# P27.net
KiCad netlist of a schematic drawn in EAGLE
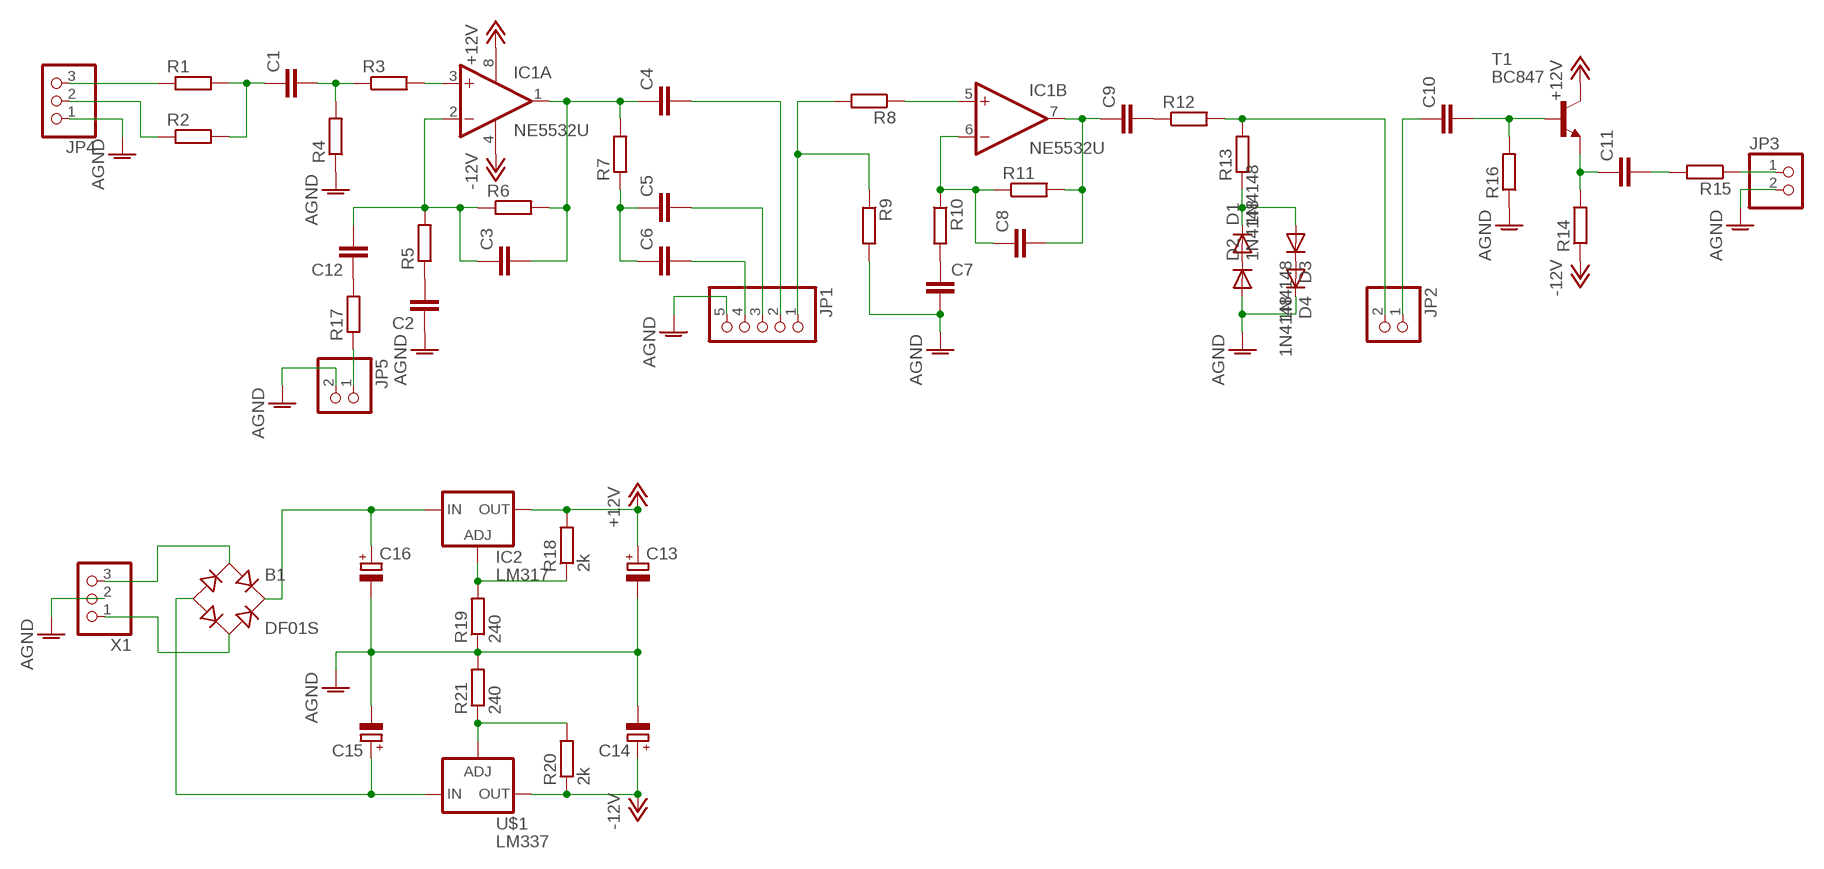
[diagram p0: schematic, sheet 1]

(export (version "E")
  (design (tool "Eeschema 10.0.6"))
  (components
    (comp (ref "B1")
      (value "DF01S")
      (footprint "eagle-import:DFS")
      (libsource (lib "eagle-import") (part "DFS01"))
    )
    (comp (ref "C1")
      (value "C-EUC0805K")
      (footprint "eagle-import:C0805K")
      (libsource (lib "eagle-import") (part "C-EUC0805K"))
    )
    (comp (ref "C2")
      (value "C-EUC0805K")
      (footprint "eagle-import:C0805K")
      (libsource (lib "eagle-import") (part "C-EUC0805K"))
    )
    (comp (ref "C3")
      (value "C-EUC0805K")
      (footprint "eagle-import:C0805K")
      (libsource (lib "eagle-import") (part "C-EUC0805K"))
    )
    (comp (ref "C4")
      (value "C-EUC0805K")
      (footprint "eagle-import:C0805K")
      (libsource (lib "eagle-import") (part "C-EUC0805K"))
    )
    (comp (ref "C5")
      (value "C-EUC0805K")
      (footprint "eagle-import:C0805K")
      (libsource (lib "eagle-import") (part "C-EUC0805K"))
    )
    (comp (ref "C6")
      (value "C-EUC0805K")
      (footprint "eagle-import:C0805K")
      (libsource (lib "eagle-import") (part "C-EUC0805K"))
    )
    (comp (ref "C7")
      (value "C-EUC0805K")
      (footprint "eagle-import:C0805K")
      (libsource (lib "eagle-import") (part "C-EUC0805K"))
    )
    (comp (ref "C8")
      (value "C-EUC0805K")
      (footprint "eagle-import:C0805K")
      (libsource (lib "eagle-import") (part "C-EUC0805K"))
    )
    (comp (ref "C9")
      (value "C-EUC0805K")
      (footprint "eagle-import:C0805K")
      (libsource (lib "eagle-import") (part "C-EUC0805K"))
    )
    (comp (ref "C10")
      (value "C-EUC0805K")
      (footprint "eagle-import:C0805K")
      (libsource (lib "eagle-import") (part "C-EUC0805K"))
    )
    (comp (ref "C11")
      (value "C-EUC0805K")
      (footprint "eagle-import:C0805K")
      (libsource (lib "eagle-import") (part "C-EUC0805K"))
    )
    (comp (ref "C12")
      (value "C-EUC0805K")
      (footprint "eagle-import:C0805K")
      (libsource (lib "eagle-import") (part "C-EUC0805K"))
    )
    (comp (ref "C13")
      (value "CPOL-EUD")
      (footprint "eagle-import:PANASONIC_D")
      (libsource (lib "eagle-import") (part "CPOL-EUD"))
    )
    (comp (ref "C14")
      (value "CPOL-EUD")
      (footprint "eagle-import:PANASONIC_D")
      (libsource (lib "eagle-import") (part "CPOL-EUD"))
    )
    (comp (ref "C15")
      (value "CPOL-EUD")
      (footprint "eagle-import:PANASONIC_D")
      (libsource (lib "eagle-import") (part "CPOL-EUD"))
    )
    (comp (ref "C16")
      (value "CPOL-EUD")
      (footprint "eagle-import:PANASONIC_D")
      (libsource (lib "eagle-import") (part "CPOL-EUD"))
    )
    (comp (ref "D1")
      (value "1N4148")
      (footprint "eagle-import:D0805")
      (libsource (lib "eagle-import") (part "1N4148"))
    )
    (comp (ref "D2")
      (value "1N4148")
      (footprint "eagle-import:D0805")
      (libsource (lib "eagle-import") (part "1N4148"))
    )
    (comp (ref "D3")
      (value "1N4148")
      (footprint "eagle-import:D0805")
      (libsource (lib "eagle-import") (part "1N4148"))
    )
    (comp (ref "D4")
      (value "1N4148")
      (footprint "eagle-import:D0805")
      (libsource (lib "eagle-import") (part "1N4148"))
    )
    (comp (ref "IC1")
      (value "NE5532U")
      (footprint "eagle-import:SO08")
      (libsource (lib "eagle-import") (part "NE5532U"))
    )
    (comp (ref "IC2")
      (value "LM317")
      (footprint "eagle-import:SOT223")
      (libsource (lib "eagle-import") (part "LM317"))
    )
    (comp (ref "JP1")
      (value "PINHD-1X5")
      (footprint "eagle-import:1X05")
      (libsource (lib "eagle-import") (part "PINHD-1X5"))
    )
    (comp (ref "JP2")
      (value "PINHD-1X2")
      (footprint "eagle-import:1X02")
      (libsource (lib "eagle-import") (part "PINHD-1X2"))
    )
    (comp (ref "JP3")
      (value "PINHD-1X2")
      (footprint "eagle-import:1X02")
      (libsource (lib "eagle-import") (part "PINHD-1X2"))
    )
    (comp (ref "JP4")
      (value "PINHD-1X3180")
      (footprint "eagle-import:1X03")
      (libsource (lib "eagle-import") (part "PINHD-1X3180"))
    )
    (comp (ref "JP5")
      (value "PINHD-1X2")
      (footprint "eagle-import:1X02")
      (libsource (lib "eagle-import") (part "PINHD-1X2"))
    )
    (comp (ref "R1")
      (value "R-EU_0805")
      (footprint "eagle-import:R0805")
      (libsource (lib "eagle-import") (part "R-EU_0805"))
    )
    (comp (ref "R2")
      (value "R-EU_0805")
      (footprint "eagle-import:R0805")
      (libsource (lib "eagle-import") (part "R-EU_0805"))
    )
    (comp (ref "R3")
      (value "R-EU_0805")
      (footprint "eagle-import:R0805")
      (libsource (lib "eagle-import") (part "R-EU_0805"))
    )
    (comp (ref "R4")
      (value "R-EU_0805")
      (footprint "eagle-import:R0805")
      (libsource (lib "eagle-import") (part "R-EU_0805"))
    )
    (comp (ref "R5")
      (value "R-EU_0805")
      (footprint "eagle-import:R0805")
      (libsource (lib "eagle-import") (part "R-EU_0805"))
    )
    (comp (ref "R6")
      (value "R-EU_0805")
      (footprint "eagle-import:R0805")
      (libsource (lib "eagle-import") (part "R-EU_0805"))
    )
    (comp (ref "R7")
      (value "R-EU_0805")
      (footprint "eagle-import:R0805")
      (libsource (lib "eagle-import") (part "R-EU_0805"))
    )
    (comp (ref "R8")
      (value "R-EU_0805")
      (footprint "eagle-import:R0805")
      (libsource (lib "eagle-import") (part "R-EU_0805"))
    )
    (comp (ref "R9")
      (value "R-EU_0805")
      (footprint "eagle-import:R0805")
      (libsource (lib "eagle-import") (part "R-EU_0805"))
    )
    (comp (ref "R10")
      (value "R-EU_0805")
      (footprint "eagle-import:R0805")
      (libsource (lib "eagle-import") (part "R-EU_0805"))
    )
    (comp (ref "R11")
      (value "R-EU_0805")
      (footprint "eagle-import:R0805")
      (libsource (lib "eagle-import") (part "R-EU_0805"))
    )
    (comp (ref "R12")
      (value "R-EU_0805")
      (footprint "eagle-import:R0805")
      (libsource (lib "eagle-import") (part "R-EU_0805"))
    )
    (comp (ref "R13")
      (value "R-EU_0805")
      (footprint "eagle-import:R0805")
      (libsource (lib "eagle-import") (part "R-EU_0805"))
    )
    (comp (ref "R14")
      (value "R-EU_0805")
      (footprint "eagle-import:R0805")
      (libsource (lib "eagle-import") (part "R-EU_0805"))
    )
    (comp (ref "R15")
      (value "R-EU_0805")
      (footprint "eagle-import:R0805")
      (libsource (lib "eagle-import") (part "R-EU_0805"))
    )
    (comp (ref "R16")
      (value "R-EU_0805")
      (footprint "eagle-import:R0805")
      (libsource (lib "eagle-import") (part "R-EU_0805"))
    )
    (comp (ref "R17")
      (value "R-EU_0805")
      (footprint "eagle-import:R0805")
      (libsource (lib "eagle-import") (part "R-EU_0805"))
    )
    (comp (ref "R18")
      (value "2k")
      (footprint "eagle-import:R0805")
      (libsource (lib "eagle-import") (part "R-EU_0805"))
    )
    (comp (ref "R19")
      (value "240")
      (footprint "eagle-import:R0805")
      (libsource (lib "eagle-import") (part "R-EU_0805"))
    )
    (comp (ref "R20")
      (value "2k")
      (footprint "eagle-import:R0805")
      (libsource (lib "eagle-import") (part "R-EU_0805"))
    )
    (comp (ref "R21")
      (value "240")
      (footprint "eagle-import:R0805")
      (libsource (lib "eagle-import") (part "R-EU_0805"))
    )
    (comp (ref "T1")
      (value "BC847")
      (footprint "eagle-import:SOT23")
      (libsource (lib "eagle-import") (part "BC847"))
    )
    (comp (ref "U$1")
      (value "LM337")
      (footprint "eagle-import:SOT223")
      (libsource (lib "eagle-import") (part "LM337"))
    )
    (comp (ref "X1")
      (value "W237-103")
      (footprint "eagle-import:W237-103")
      (libsource (lib "eagle-import") (part "W237-103"))
    )
  )
  (nets
    (net (code "1") (name "+12V") (class "Default")
      (node (ref "C13") (pin "+") (pinfunction "+_+") (pintype "passive"))
      (node (ref "IC1") (pin "8") (pinfunction "V+_8") (pintype "power_in"))
      (node (ref "IC2") (pin "2") (pinfunction "OUT_2") (pintype "passive"))
      (node (ref "IC2") (pin "4") (pinfunction "OUT_4") (pintype "passive"))
      (node (ref "R18") (pin "2") (pinfunction "2_2") (pintype "passive"))
      (node (ref "T1") (pin "3") (pinfunction "C_3") (pintype "passive"))
    )
    (net (code "2") (name "-12V") (class "Default")
      (node (ref "C14") (pin "+") (pinfunction "+_+") (pintype "passive"))
      (node (ref "IC1") (pin "4") (pinfunction "V-_4") (pintype "power_in"))
      (node (ref "R14") (pin "1") (pinfunction "1_1") (pintype "passive"))
      (node (ref "R20") (pin "1") (pinfunction "1_1") (pintype "passive"))
      (node (ref "U$1") (pin "3") (pinfunction "OUT_3") (pintype "passive"))
    )
    (net (code "3") (name "AGND") (class "Default")
      (node (ref "C13") (pin "-") (pinfunction "-_-") (pintype "passive"))
      (node (ref "C14") (pin "-") (pinfunction "-_-") (pintype "passive"))
      (node (ref "C15") (pin "-") (pinfunction "-_-") (pintype "passive"))
      (node (ref "C16") (pin "-") (pinfunction "-_-") (pintype "passive"))
      (node (ref "C2") (pin "1") (pinfunction "1_1") (pintype "passive"))
      (node (ref "C7") (pin "2") (pinfunction "2_2") (pintype "passive"))
      (node (ref "D2") (pin "A") (pinfunction "A_A") (pintype "passive"))
      (node (ref "D4") (pin "K") (pinfunction "C_K") (pintype "passive"))
      (node (ref "JP1") (pin "5") (pinfunction "5_5") (pintype "passive"))
      (node (ref "JP3") (pin "2") (pinfunction "2_2") (pintype "passive"))
      (node (ref "JP4") (pin "1") (pinfunction "1_1") (pintype "passive"))
      (node (ref "JP5") (pin "2") (pinfunction "2_2") (pintype "passive"))
      (node (ref "R16") (pin "1") (pinfunction "1_1") (pintype "passive"))
      (node (ref "R19") (pin "1") (pinfunction "1_1") (pintype "passive"))
      (node (ref "R21") (pin "2") (pinfunction "2_2") (pintype "passive"))
      (node (ref "R4") (pin "1") (pinfunction "1_1") (pintype "passive"))
      (node (ref "R9") (pin "2") (pinfunction "2_2") (pintype "passive"))
      (node (ref "X1") (pin "2") (pinfunction "2_2") (pintype "passive"))
    )
    (net (code "4") (name "Net-(B1-Pad-)") (class "Default")
      (node (ref "B1") (pin "-") (pinfunction "-_-") (pintype "passive"))
      (node (ref "C15") (pin "+") (pinfunction "+_+") (pintype "passive"))
      (node (ref "U$1") (pin "2") (pinfunction "IN_2") (pintype "input"))
      (node (ref "U$1") (pin "4") (pinfunction "IN_4") (pintype "input"))
    )
    (net (code "5") (name "Net-(B1-PadAC1)") (class "Default")
      (node (ref "B1") (pin "AC1") (pinfunction "AC1_AC1") (pintype "passive"))
      (node (ref "X1") (pin "3") (pinfunction "3_3") (pintype "passive"))
    )
    (net (code "6") (name "Net-(B1-PadAC2)") (class "Default")
      (node (ref "B1") (pin "AC2") (pinfunction "AC2_AC2") (pintype "passive"))
      (node (ref "X1") (pin "1") (pinfunction "1_1") (pintype "passive"))
    )
    (net (code "7") (name "Net-(C1-Pad1)") (class "Default")
      (node (ref "C1") (pin "1") (pinfunction "1_1") (pintype "passive"))
      (node (ref "R1") (pin "2") (pinfunction "2_2") (pintype "passive"))
      (node (ref "R2") (pin "2") (pinfunction "2_2") (pintype "passive"))
    )
    (net (code "8") (name "Net-(C1-Pad2)") (class "Default")
      (node (ref "C1") (pin "2") (pinfunction "2_2") (pintype "passive"))
      (node (ref "R3") (pin "1") (pinfunction "1_1") (pintype "passive"))
      (node (ref "R4") (pin "2") (pinfunction "2_2") (pintype "passive"))
    )
    (net (code "9") (name "Net-(C2-Pad2)") (class "Default")
      (node (ref "C2") (pin "2") (pinfunction "2_2") (pintype "passive"))
      (node (ref "R5") (pin "1") (pinfunction "1_1") (pintype "passive"))
    )
    (net (code "10") (name "Net-(C4-Pad2)") (class "Default")
      (node (ref "C4") (pin "2") (pinfunction "2_2") (pintype "passive"))
      (node (ref "JP1") (pin "2") (pinfunction "2_2") (pintype "passive"))
    )
    (net (code "11") (name "Net-(C5-Pad1)") (class "Default")
      (node (ref "C5") (pin "1") (pinfunction "1_1") (pintype "passive"))
      (node (ref "C6") (pin "1") (pinfunction "1_1") (pintype "passive"))
      (node (ref "R7") (pin "1") (pinfunction "1_1") (pintype "passive"))
    )
    (net (code "12") (name "Net-(C5-Pad2)") (class "Default")
      (node (ref "C5") (pin "2") (pinfunction "2_2") (pintype "passive"))
      (node (ref "JP1") (pin "3") (pinfunction "3_3") (pintype "passive"))
    )
    (net (code "13") (name "Net-(C6-Pad2)") (class "Default")
      (node (ref "C6") (pin "2") (pinfunction "2_2") (pintype "passive"))
      (node (ref "JP1") (pin "4") (pinfunction "4_4") (pintype "passive"))
    )
    (net (code "14") (name "Net-(C7-Pad1)") (class "Default")
      (node (ref "C7") (pin "1") (pinfunction "1_1") (pintype "passive"))
      (node (ref "R10") (pin "2") (pinfunction "2_2") (pintype "passive"))
    )
    (net (code "15") (name "Net-(C9-Pad2)") (class "Default")
      (node (ref "C9") (pin "2") (pinfunction "2_2") (pintype "passive"))
      (node (ref "R12") (pin "1") (pinfunction "1_1") (pintype "passive"))
    )
    (net (code "16") (name "Net-(C10-Pad1)") (class "Default")
      (node (ref "C10") (pin "1") (pinfunction "1_1") (pintype "passive"))
      (node (ref "JP2") (pin "1") (pinfunction "1_1") (pintype "passive"))
    )
    (net (code "17") (name "Net-(C11-Pad2)") (class "Default")
      (node (ref "C11") (pin "2") (pinfunction "2_2") (pintype "passive"))
      (node (ref "R15") (pin "2") (pinfunction "2_2") (pintype "passive"))
    )
    (net (code "18") (name "Net-(C12-Pad1)") (class "Default")
      (node (ref "C12") (pin "1") (pinfunction "1_1") (pintype "passive"))
      (node (ref "R17") (pin "2") (pinfunction "2_2") (pintype "passive"))
    )
    (net (code "19") (name "Net-(D1-C)") (class "Default")
      (node (ref "D1") (pin "K") (pinfunction "C_K") (pintype "passive"))
      (node (ref "D3") (pin "A") (pinfunction "A_A") (pintype "passive"))
      (node (ref "R13") (pin "1") (pinfunction "1_1") (pintype "passive"))
    )
    (net (code "20") (name "Net-(D2-C)") (class "Default")
      (node (ref "D1") (pin "A") (pinfunction "A_A") (pintype "passive"))
      (node (ref "D2") (pin "K") (pinfunction "C_K") (pintype "passive"))
    )
    (net (code "21") (name "Net-(D3-C)") (class "Default")
      (node (ref "D3") (pin "K") (pinfunction "C_K") (pintype "passive"))
      (node (ref "D4") (pin "A") (pinfunction "A_A") (pintype "passive"))
    )
    (net (code "22") (name "Net-(IC1A-+IN)") (class "Default")
      (node (ref "IC1") (pin "3") (pinfunction "+IN_3") (pintype "input"))
      (node (ref "R3") (pin "2") (pinfunction "2_2") (pintype "passive"))
    )
    (net (code "23") (name "Net-(IC1A--IN)") (class "Default")
      (node (ref "C12") (pin "2") (pinfunction "2_2") (pintype "passive"))
      (node (ref "C3") (pin "1") (pinfunction "1_1") (pintype "passive"))
      (node (ref "IC1") (pin "2") (pinfunction "-IN_2") (pintype "input"))
      (node (ref "R5") (pin "2") (pinfunction "2_2") (pintype "passive"))
      (node (ref "R6") (pin "1") (pinfunction "1_1") (pintype "passive"))
    )
    (net (code "24") (name "Net-(IC1A-OUT)") (class "Default")
      (node (ref "C3") (pin "2") (pinfunction "2_2") (pintype "passive"))
      (node (ref "C4") (pin "1") (pinfunction "1_1") (pintype "passive"))
      (node (ref "IC1") (pin "1") (pinfunction "OUT_1") (pintype "output"))
      (node (ref "R6") (pin "2") (pinfunction "2_2") (pintype "passive"))
      (node (ref "R7") (pin "2") (pinfunction "2_2") (pintype "passive"))
    )
    (net (code "25") (name "Net-(IC1B-+IN)") (class "Default")
      (node (ref "IC1") (pin "5") (pinfunction "+IN_5") (pintype "input"))
      (node (ref "R8") (pin "1") (pinfunction "1_1") (pintype "passive"))
    )
    (net (code "26") (name "Net-(IC1B--IN)") (class "Default")
      (node (ref "C8") (pin "1") (pinfunction "1_1") (pintype "passive"))
      (node (ref "IC1") (pin "6") (pinfunction "-IN_6") (pintype "input"))
      (node (ref "R10") (pin "1") (pinfunction "1_1") (pintype "passive"))
      (node (ref "R11") (pin "1") (pinfunction "1_1") (pintype "passive"))
    )
    (net (code "27") (name "Net-(IC1B-OUT)") (class "Default")
      (node (ref "C8") (pin "2") (pinfunction "2_2") (pintype "passive"))
      (node (ref "C9") (pin "1") (pinfunction "1_1") (pintype "passive"))
      (node (ref "IC1") (pin "7") (pinfunction "OUT_7") (pintype "output"))
      (node (ref "R11") (pin "2") (pinfunction "2_2") (pintype "passive"))
    )
    (net (code "28") (name "Net-(IC2-ADJ)") (class "Default")
      (node (ref "IC2") (pin "1") (pinfunction "ADJ_1") (pintype "input"))
      (node (ref "R18") (pin "1") (pinfunction "1_1") (pintype "passive"))
      (node (ref "R19") (pin "2") (pinfunction "2_2") (pintype "passive"))
    )
    (net (code "29") (name "Net-(IC2-IN)") (class "Default")
      (node (ref "B1") (pin "+") (pinfunction "+_+") (pintype "passive"))
      (node (ref "C16") (pin "+") (pinfunction "+_+") (pintype "passive"))
      (node (ref "IC2") (pin "3") (pinfunction "IN_3") (pintype "input"))
    )
    (net (code "30") (name "Net-(JP1-Pad1)") (class "Default")
      (node (ref "JP1") (pin "1") (pinfunction "1_1") (pintype "passive"))
      (node (ref "R8") (pin "2") (pinfunction "2_2") (pintype "passive"))
      (node (ref "R9") (pin "1") (pinfunction "1_1") (pintype "passive"))
    )
    (net (code "31") (name "Net-(JP2-Pad2)") (class "Default")
      (node (ref "JP2") (pin "2") (pinfunction "2_2") (pintype "passive"))
      (node (ref "R12") (pin "2") (pinfunction "2_2") (pintype "passive"))
      (node (ref "R13") (pin "2") (pinfunction "2_2") (pintype "passive"))
    )
    (net (code "32") (name "Net-(JP3-Pad1)") (class "Default")
      (node (ref "JP3") (pin "1") (pinfunction "1_1") (pintype "passive"))
      (node (ref "R15") (pin "1") (pinfunction "1_1") (pintype "passive"))
    )
    (net (code "33") (name "Net-(JP4-Pad2)") (class "Default")
      (node (ref "JP4") (pin "2") (pinfunction "2_2") (pintype "passive"))
      (node (ref "R2") (pin "1") (pinfunction "1_1") (pintype "passive"))
    )
    (net (code "34") (name "Net-(JP4-Pad3)") (class "Default")
      (node (ref "JP4") (pin "3") (pinfunction "3_3") (pintype "passive"))
      (node (ref "R1") (pin "1") (pinfunction "1_1") (pintype "passive"))
    )
    (net (code "35") (name "Net-(JP5-Pad1)") (class "Default")
      (node (ref "JP5") (pin "1") (pinfunction "1_1") (pintype "passive"))
      (node (ref "R17") (pin "1") (pinfunction "1_1") (pintype "passive"))
    )
    (net (code "36") (name "Net-(T1-B)") (class "Default")
      (node (ref "C10") (pin "2") (pinfunction "2_2") (pintype "passive"))
      (node (ref "R16") (pin "2") (pinfunction "2_2") (pintype "passive"))
      (node (ref "T1") (pin "1") (pinfunction "B_1") (pintype "passive"))
    )
    (net (code "37") (name "Net-(T1-E)") (class "Default")
      (node (ref "C11") (pin "1") (pinfunction "1_1") (pintype "passive"))
      (node (ref "R14") (pin "2") (pinfunction "2_2") (pintype "passive"))
      (node (ref "T1") (pin "2") (pinfunction "E_2") (pintype "passive"))
    )
    (net (code "38") (name "Net-(U$1-ADJ)") (class "Default")
      (node (ref "R20") (pin "2") (pinfunction "2_2") (pintype "passive"))
      (node (ref "R21") (pin "1") (pinfunction "1_1") (pintype "passive"))
      (node (ref "U$1") (pin "1") (pinfunction "ADJ_1") (pintype "input"))
    )
  )
)
